# Module_MCU_M5Stack.net
KiCad netlist of a schematic drawn in EAGLE
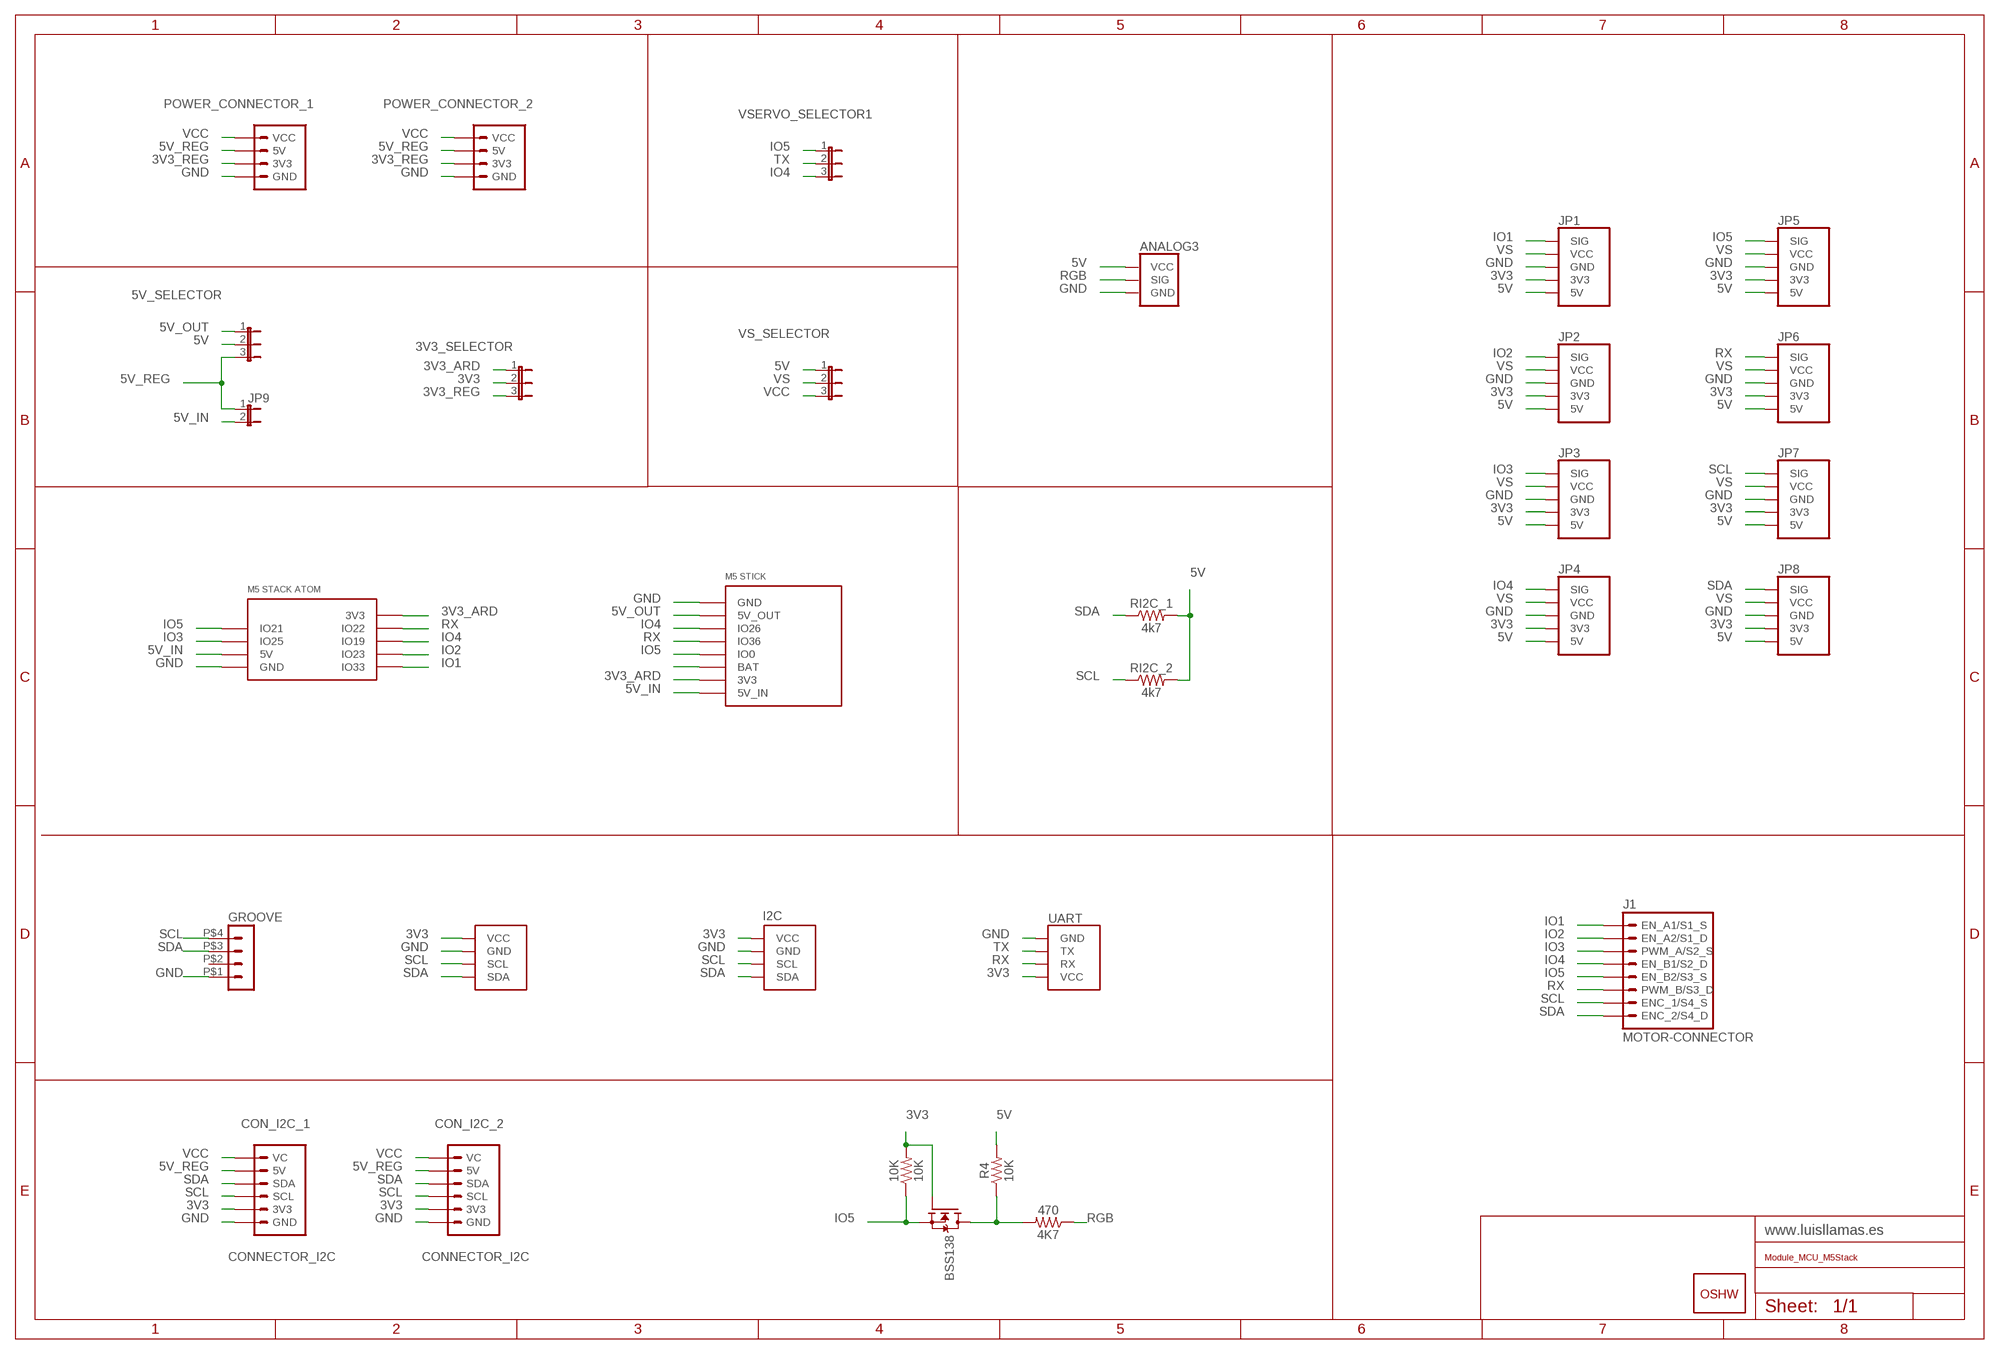
[diagram p0: schematic, sheet 1]

(export (version "E")
  (design (tool "Eeschema 10.0.6"))
  (components
    (comp (ref "3V3_SELECTOR")
      (value "JUMPER_3")
      (footprint "eagle-import:JUMPER_3")
      (libsource (lib "eagle-import") (part "JUMPER_3"))
    )
    (comp (ref "4K7")
      (value "470")
      (footprint "eagle-import:0805")
      (libsource (lib "eagle-import") (part "RESISTOR0805"))
    )
    (comp (ref "5V_SELECTOR")
      (value "JUMPER_3")
      (footprint "eagle-import:JUMPER_3")
      (libsource (lib "eagle-import") (part "JUMPER_3"))
    )
    (comp (ref "10K")
      (value "10K")
      (footprint "eagle-import:0805")
      (libsource (lib "eagle-import") (part "RESISTOR0805"))
    )
    (comp (ref "ANALOG3")
      (value "LDR/OCT")
      (footprint "eagle-import:LDR")
      (libsource (lib "eagle-import") (part "LDR/OCT"))
    )
    (comp (ref "BSS138")
      (value "MOSFET-N-SOT23")
      (footprint "eagle-import:SOT23")
      (libsource (lib "eagle-import") (part "MOSFET-N-SOT23"))
    )
    (comp (ref "CON_I2C_1")
      (value "CONNECTOR_I2C")
      (footprint "eagle-import:CONNECTOR_I2C")
      (libsource (lib "eagle-import") (part "CONNECTOR_I2C"))
    )
    (comp (ref "CON_I2C_2")
      (value "CONNECTOR_I2C")
      (footprint "eagle-import:CONNECTOR_I2C")
      (libsource (lib "eagle-import") (part "CONNECTOR_I2C"))
    )
    (comp (ref "GOLD_ORB_SM1")
      (value "OSHWLOGO_GOLD_ORB_MED")
      (footprint "eagle-import:OSHW1")
      (libsource (lib "eagle-import") (part "OSHWLOGO_GOLD_ORB_MED"))
    )
    (comp (ref "GROOVE")
      (value "GROOVE")
      (footprint "eagle-import:GROOVE")
      (libsource (lib "eagle-import") (part "GROOVE"))
    )
    (comp (ref "I2C_1")
      (value "I2C")
      (footprint "eagle-import:I2C_VCC_GND_SCL_SDA")
      (libsource (lib "eagle-import") (part "GENERIC_I2CVCC_GND_SCL_SDA"))
    )
    (comp (ref "I2C_2")
      (value "GENERIC_I2CVCC_GND_SCL_SDA")
      (footprint "eagle-import:I2C_VCC_GND_SCL_SDA")
      (libsource (lib "eagle-import") (part "GENERIC_I2CVCC_GND_SCL_SDA"))
    )
    (comp (ref "J1")
      (value "MOTOR-CONNECTOR")
      (footprint "eagle-import:MOTOR-CONNECTOR")
      (libsource (lib "eagle-import") (part "MOTOR-CONNECTOR"))
    )
    (comp (ref "JP1")
      (value "SERVO_5")
      (footprint "eagle-import:SERVO_5")
      (libsource (lib "eagle-import") (part "SERVO_5"))
    )
    (comp (ref "JP2")
      (value "SERVO_5")
      (footprint "eagle-import:SERVO_5")
      (libsource (lib "eagle-import") (part "SERVO_5"))
    )
    (comp (ref "JP3")
      (value "SERVO_5")
      (footprint "eagle-import:SERVO_5")
      (libsource (lib "eagle-import") (part "SERVO_5"))
    )
    (comp (ref "JP4")
      (value "SERVO_5")
      (footprint "eagle-import:SERVO_5")
      (libsource (lib "eagle-import") (part "SERVO_5"))
    )
    (comp (ref "JP5")
      (value "SERVO_5")
      (footprint "eagle-import:SERVO_5")
      (libsource (lib "eagle-import") (part "SERVO_5"))
    )
    (comp (ref "JP6")
      (value "SERVO_5")
      (footprint "eagle-import:SERVO_5")
      (libsource (lib "eagle-import") (part "SERVO_5"))
    )
    (comp (ref "JP7")
      (value "SERVO_5")
      (footprint "eagle-import:SERVO_5")
      (libsource (lib "eagle-import") (part "SERVO_5"))
    )
    (comp (ref "JP8")
      (value "SERVO_5")
      (footprint "eagle-import:SERVO_5")
      (libsource (lib "eagle-import") (part "SERVO_5"))
    )
    (comp (ref "JP9")
      (value "JUMPER_2PTH")
      (footprint "eagle-import:JUMPER_2")
      (libsource (lib "eagle-import") (part "JUMPER_2PTH"))
    )
    (comp (ref "POWER_CONNECTOR_1")
      (value "POWER-CONNECTOR")
      (footprint "eagle-import:POWER-CONNECTOR")
      (libsource (lib "eagle-import") (part "POWER-CONNECTOR"))
    )
    (comp (ref "POWER_CONNECTOR_2")
      (value "POWER-CONNECTOR")
      (footprint "eagle-import:POWER-CONNECTOR")
      (libsource (lib "eagle-import") (part "POWER-CONNECTOR"))
    )
    (comp (ref "R4")
      (value "10K")
      (footprint "eagle-import:0805")
      (libsource (lib "eagle-import") (part "RESISTOR0805"))
    )
    (comp (ref "RI2C_1")
      (value "4k7")
      (footprint "eagle-import:1206")
      (libsource (lib "eagle-import") (part "RESISTOR1206"))
    )
    (comp (ref "RI2C_2")
      (value "4k7")
      (footprint "eagle-import:1206")
      (libsource (lib "eagle-import") (part "RESISTOR1206"))
    )
    (comp (ref "U$1")
      (value "M5-STACK-ATOM")
      (footprint "eagle-import:M5-STACK-ATOM")
      (libsource (lib "eagle-import") (part "M5-STACK-ATOM"))
    )
    (comp (ref "U$2")
      (value "M5-STICK")
      (footprint "eagle-import:M5-STICK")
      (libsource (lib "eagle-import") (part "M5-STICK"))
    )
    (comp (ref "UART")
      (value "UART")
      (footprint "eagle-import:GENERIC_UART")
      (libsource (lib "eagle-import") (part "GENERIC_UARTGND_TX_RX_VCC"))
    )
    (comp (ref "VSERVO_SELECTOR1")
      (value "JUMPER_3")
      (footprint "eagle-import:JUMPER_3")
      (libsource (lib "eagle-import") (part "JUMPER_3"))
    )
    (comp (ref "VS_SELECTOR")
      (value "JUMPER_3")
      (footprint "eagle-import:JUMPER_3")
      (libsource (lib "eagle-import") (part "JUMPER_3"))
    )
  )
  (nets
    (net (code "1") (name "/3V3") (class "Default")
      (node (ref "10K") (pin "2") (pinfunction "2_2") (pintype "passive"))
      (node (ref "3V3_SELECTOR") (pin "2") (pinfunction "2_2") (pintype "passive"))
      (node (ref "BSS138") (pin "1") (pinfunction "G_1") (pintype "passive"))
      (node (ref "CON_I2C_1") (pin "3V3") (pinfunction "3V3_3V3") (pintype "passive"))
      (node (ref "CON_I2C_2") (pin "3V3") (pinfunction "3V3_3V3") (pintype "passive"))
      (node (ref "I2C_1") (pin "VCC") (pinfunction "VCC_VCC") (pintype "power_in"))
      (node (ref "I2C_2") (pin "VCC") (pinfunction "VCC_VCC") (pintype "power_in"))
      (node (ref "JP1") (pin "3V3") (pinfunction "3V3_3V3") (pintype "power_in"))
      (node (ref "JP2") (pin "3V3") (pinfunction "3V3_3V3") (pintype "power_in"))
      (node (ref "JP3") (pin "3V3") (pinfunction "3V3_3V3") (pintype "power_in"))
      (node (ref "JP4") (pin "3V3") (pinfunction "3V3_3V3") (pintype "power_in"))
      (node (ref "JP5") (pin "3V3") (pinfunction "3V3_3V3") (pintype "power_in"))
      (node (ref "JP6") (pin "3V3") (pinfunction "3V3_3V3") (pintype "power_in"))
      (node (ref "JP7") (pin "3V3") (pinfunction "3V3_3V3") (pintype "power_in"))
      (node (ref "JP8") (pin "3V3") (pinfunction "3V3_3V3") (pintype "power_in"))
      (node (ref "UART") (pin "VCC") (pinfunction "VCC_VCC") (pintype "bidirectional"))
    )
    (net (code "2") (name "/3V3_ARD") (class "Default")
      (node (ref "3V3_SELECTOR") (pin "1") (pinfunction "1_1") (pintype "passive"))
      (node (ref "U$1") (pin "3V3") (pinfunction "3V3_3V3") (pintype "bidirectional"))
      (node (ref "U$2") (pin "3V3") (pinfunction "3V3_3V3") (pintype "bidirectional"))
    )
    (net (code "3") (name "/3V3_REG") (class "Default")
      (node (ref "3V3_SELECTOR") (pin "3") (pinfunction "3_3") (pintype "passive"))
      (node (ref "POWER_CONNECTOR_1") (pin "3V3") (pinfunction "3V3_3V3") (pintype "passive"))
      (node (ref "POWER_CONNECTOR_2") (pin "3V3") (pinfunction "3V3_3V3") (pintype "passive"))
    )
    (net (code "4") (name "/5V") (class "Default")
      (node (ref "5V_SELECTOR") (pin "2") (pinfunction "2_2") (pintype "passive"))
      (node (ref "ANALOG3") (pin "VCC") (pinfunction "VCC_VCC") (pintype "power_in"))
      (node (ref "JP1") (pin "5V") (pinfunction "5V_5V") (pintype "power_in"))
      (node (ref "JP2") (pin "5V") (pinfunction "5V_5V") (pintype "power_in"))
      (node (ref "JP3") (pin "5V") (pinfunction "5V_5V") (pintype "power_in"))
      (node (ref "JP4") (pin "5V") (pinfunction "5V_5V") (pintype "power_in"))
      (node (ref "JP5") (pin "5V") (pinfunction "5V_5V") (pintype "power_in"))
      (node (ref "JP6") (pin "5V") (pinfunction "5V_5V") (pintype "power_in"))
      (node (ref "JP7") (pin "5V") (pinfunction "5V_5V") (pintype "power_in"))
      (node (ref "JP8") (pin "5V") (pinfunction "5V_5V") (pintype "power_in"))
      (node (ref "R4") (pin "2") (pinfunction "2_2") (pintype "passive"))
      (node (ref "RI2C_1") (pin "2") (pinfunction "2_2") (pintype "passive"))
      (node (ref "RI2C_2") (pin "2") (pinfunction "2_2") (pintype "passive"))
      (node (ref "VS_SELECTOR") (pin "1") (pinfunction "1_1") (pintype "passive"))
    )
    (net (code "5") (name "/5V_IN") (class "Default")
      (node (ref "JP9") (pin "2") (pinfunction "2_2") (pintype "passive"))
      (node (ref "U$1") (pin "5V") (pinfunction "5V_5V") (pintype "bidirectional"))
      (node (ref "U$2") (pin "5V_IN") (pinfunction "5V_IN_5V_IN") (pintype "bidirectional"))
    )
    (net (code "6") (name "/5V_OUT") (class "Default")
      (node (ref "5V_SELECTOR") (pin "1") (pinfunction "1_1") (pintype "passive"))
      (node (ref "U$2") (pin "5V_OUT") (pinfunction "5V_OUT_5V_OUT") (pintype "bidirectional"))
    )
    (net (code "7") (name "/5V_REG") (class "Default")
      (node (ref "5V_SELECTOR") (pin "3") (pinfunction "3_3") (pintype "passive"))
      (node (ref "CON_I2C_1") (pin "5V") (pinfunction "5V_5V") (pintype "passive"))
      (node (ref "CON_I2C_2") (pin "5V") (pinfunction "5V_5V") (pintype "passive"))
      (node (ref "JP9") (pin "1") (pinfunction "1_1") (pintype "passive"))
      (node (ref "POWER_CONNECTOR_1") (pin "5V") (pinfunction "5V_5V") (pintype "passive"))
      (node (ref "POWER_CONNECTOR_2") (pin "5V") (pinfunction "5V_5V") (pintype "passive"))
    )
    (net (code "8") (name "/GND") (class "Default")
      (node (ref "ANALOG3") (pin "GND") (pinfunction "GND_GND") (pintype "power_in"))
      (node (ref "CON_I2C_1") (pin "GND") (pinfunction "GND_GND") (pintype "passive"))
      (node (ref "CON_I2C_2") (pin "GND") (pinfunction "GND_GND") (pintype "passive"))
      (node (ref "GROOVE") (pin "P$1") (pinfunction "1_P$1") (pintype "passive"))
      (node (ref "I2C_1") (pin "GND") (pinfunction "GND_GND") (pintype "power_in"))
      (node (ref "I2C_2") (pin "GND") (pinfunction "GND_GND") (pintype "power_in"))
      (node (ref "JP1") (pin "GND") (pinfunction "GND_GND") (pintype "power_in"))
      (node (ref "JP2") (pin "GND") (pinfunction "GND_GND") (pintype "power_in"))
      (node (ref "JP3") (pin "GND") (pinfunction "GND_GND") (pintype "power_in"))
      (node (ref "JP4") (pin "GND") (pinfunction "GND_GND") (pintype "power_in"))
      (node (ref "JP5") (pin "GND") (pinfunction "GND_GND") (pintype "power_in"))
      (node (ref "JP6") (pin "GND") (pinfunction "GND_GND") (pintype "power_in"))
      (node (ref "JP7") (pin "GND") (pinfunction "GND_GND") (pintype "power_in"))
      (node (ref "JP8") (pin "GND") (pinfunction "GND_GND") (pintype "power_in"))
      (node (ref "POWER_CONNECTOR_1") (pin "GND") (pinfunction "GND_GND") (pintype "passive"))
      (node (ref "POWER_CONNECTOR_2") (pin "GND") (pinfunction "GND_GND") (pintype "passive"))
      (node (ref "U$1") (pin "GND") (pinfunction "GND_GND") (pintype "bidirectional"))
      (node (ref "U$2") (pin "GND") (pinfunction "GND_GND") (pintype "bidirectional"))
      (node (ref "UART") (pin "GND") (pinfunction "GND_GND") (pintype "power_in"))
    )
    (net (code "9") (name "/IO1") (class "Default")
      (node (ref "J1") (pin "EN_A1/S1_S") (pinfunction "EN_A1/S1_S_EN_A1/S1_S") (pintype "passive"))
      (node (ref "JP1") (pin "SIG") (pinfunction "SIG_SIG") (pintype "bidirectional"))
      (node (ref "U$1") (pin "IO33") (pinfunction "IO33_IO33") (pintype "bidirectional"))
    )
    (net (code "10") (name "/IO2") (class "Default")
      (node (ref "J1") (pin "EN_A2/S1_D") (pinfunction "EN_A2/S1_D_EN_A2/S1_D") (pintype "passive"))
      (node (ref "JP2") (pin "SIG") (pinfunction "SIG_SIG") (pintype "bidirectional"))
      (node (ref "U$1") (pin "IO23") (pinfunction "IO23_IO23") (pintype "bidirectional"))
    )
    (net (code "11") (name "/IO3") (class "Default")
      (node (ref "J1") (pin "PWM_A/S2_S") (pinfunction "PWM_A/S2_S_PWM_A/S2_S") (pintype "passive"))
      (node (ref "JP3") (pin "SIG") (pinfunction "SIG_SIG") (pintype "bidirectional"))
      (node (ref "U$1") (pin "IO25") (pinfunction "IO25_IO25") (pintype "bidirectional"))
    )
    (net (code "12") (name "/IO4") (class "Default")
      (node (ref "J1") (pin "EN_B1/S2_D") (pinfunction "EN_B1/S2_D_EN_B1/S2_D") (pintype "passive"))
      (node (ref "JP4") (pin "SIG") (pinfunction "SIG_SIG") (pintype "bidirectional"))
      (node (ref "U$1") (pin "IO19") (pinfunction "IO19_IO19") (pintype "bidirectional"))
      (node (ref "U$2") (pin "IO26") (pinfunction "IO26_IO26") (pintype "bidirectional"))
      (node (ref "VSERVO_SELECTOR1") (pin "3") (pinfunction "3_3") (pintype "passive"))
    )
    (net (code "13") (name "/IO5") (class "Default")
      (node (ref "10K") (pin "1") (pinfunction "1_1") (pintype "passive"))
      (node (ref "BSS138") (pin "2") (pinfunction "S_2") (pintype "passive"))
      (node (ref "J1") (pin "EN_B2/S3_S") (pinfunction "EN_B2/S3_S_EN_B2/S3_S") (pintype "passive"))
      (node (ref "JP5") (pin "SIG") (pinfunction "SIG_SIG") (pintype "bidirectional"))
      (node (ref "U$1") (pin "IO21") (pinfunction "IO21_IO21") (pintype "bidirectional"))
      (node (ref "U$2") (pin "IO0") (pinfunction "IO0_IO0") (pintype "bidirectional"))
      (node (ref "VSERVO_SELECTOR1") (pin "1") (pinfunction "1_1") (pintype "passive"))
    )
    (net (code "14") (name "/RGB") (class "Default")
      (node (ref "4K7") (pin "1") (pinfunction "1_1") (pintype "passive"))
      (node (ref "ANALOG3") (pin "SIG") (pinfunction "SIG_SIG") (pintype "bidirectional"))
    )
    (net (code "15") (name "/RX") (class "Default")
      (node (ref "J1") (pin "PWM_B/S3_D") (pinfunction "PWM_B/S3_D_PWM_B/S3_D") (pintype "passive"))
      (node (ref "JP6") (pin "SIG") (pinfunction "SIG_SIG") (pintype "bidirectional"))
      (node (ref "U$1") (pin "IO22") (pinfunction "IO22_IO22") (pintype "bidirectional"))
      (node (ref "U$2") (pin "IO36") (pinfunction "IO36_IO36") (pintype "bidirectional"))
      (node (ref "UART") (pin "RX") (pinfunction "RX_RX") (pintype "bidirectional"))
    )
    (net (code "16") (name "/SCL") (class "Default")
      (node (ref "CON_I2C_1") (pin "SCL") (pinfunction "SCL_SCL") (pintype "passive"))
      (node (ref "CON_I2C_2") (pin "SCL") (pinfunction "SCL_SCL") (pintype "passive"))
      (node (ref "GROOVE") (pin "P$4") (pinfunction "4_P$4") (pintype "passive"))
      (node (ref "I2C_1") (pin "SCL") (pinfunction "SCL_SCL") (pintype "bidirectional"))
      (node (ref "I2C_2") (pin "SCL") (pinfunction "SCL_SCL") (pintype "bidirectional"))
      (node (ref "J1") (pin "ENC_1/S4_S") (pinfunction "ENC_1/S4_S_ENC_1/S4_S") (pintype "passive"))
      (node (ref "JP7") (pin "SIG") (pinfunction "SIG_SIG") (pintype "bidirectional"))
      (node (ref "RI2C_2") (pin "1") (pinfunction "1_1") (pintype "passive"))
    )
    (net (code "17") (name "/SDA") (class "Default")
      (node (ref "CON_I2C_1") (pin "SDA") (pinfunction "SDA_SDA") (pintype "passive"))
      (node (ref "CON_I2C_2") (pin "SDA") (pinfunction "SDA_SDA") (pintype "passive"))
      (node (ref "GROOVE") (pin "P$3") (pinfunction "3_P$3") (pintype "passive"))
      (node (ref "I2C_1") (pin "SDA") (pinfunction "SDA_SDA") (pintype "bidirectional"))
      (node (ref "I2C_2") (pin "SDA") (pinfunction "SDA_SDA") (pintype "bidirectional"))
      (node (ref "J1") (pin "ENC_2/S4_D") (pinfunction "ENC_2/S4_D_ENC_2/S4_D") (pintype "passive"))
      (node (ref "JP8") (pin "SIG") (pinfunction "SIG_SIG") (pintype "bidirectional"))
      (node (ref "RI2C_1") (pin "1") (pinfunction "1_1") (pintype "passive"))
    )
    (net (code "18") (name "/TX") (class "Default")
      (node (ref "UART") (pin "TX") (pinfunction "TX_TX") (pintype "power_in"))
      (node (ref "VSERVO_SELECTOR1") (pin "2") (pinfunction "2_2") (pintype "passive"))
    )
    (net (code "19") (name "/VCC") (class "Default")
      (node (ref "CON_I2C_1") (pin "VC") (pinfunction "VC_VC") (pintype "passive"))
      (node (ref "CON_I2C_2") (pin "VC") (pinfunction "VC_VC") (pintype "passive"))
      (node (ref "POWER_CONNECTOR_1") (pin "VCC") (pinfunction "VCC_VCC") (pintype "passive"))
      (node (ref "POWER_CONNECTOR_2") (pin "VCC") (pinfunction "VCC_VCC") (pintype "passive"))
      (node (ref "VS_SELECTOR") (pin "3") (pinfunction "3_3") (pintype "passive"))
    )
    (net (code "20") (name "/VS") (class "Default")
      (node (ref "JP1") (pin "VCC") (pinfunction "VCC_VCC") (pintype "power_in"))
      (node (ref "JP2") (pin "VCC") (pinfunction "VCC_VCC") (pintype "power_in"))
      (node (ref "JP3") (pin "VCC") (pinfunction "VCC_VCC") (pintype "power_in"))
      (node (ref "JP4") (pin "VCC") (pinfunction "VCC_VCC") (pintype "power_in"))
      (node (ref "JP5") (pin "VCC") (pinfunction "VCC_VCC") (pintype "power_in"))
      (node (ref "JP6") (pin "VCC") (pinfunction "VCC_VCC") (pintype "power_in"))
      (node (ref "JP7") (pin "VCC") (pinfunction "VCC_VCC") (pintype "power_in"))
      (node (ref "JP8") (pin "VCC") (pinfunction "VCC_VCC") (pintype "power_in"))
      (node (ref "VS_SELECTOR") (pin "2") (pinfunction "2_2") (pintype "passive"))
    )
    (net (code "21") (name "Net-(BSS138-D)") (class "Default")
      (node (ref "4K7") (pin "2") (pinfunction "2_2") (pintype "passive"))
      (node (ref "BSS138") (pin "3") (pinfunction "D_3") (pintype "passive"))
      (node (ref "R4") (pin "1") (pinfunction "1_1") (pintype "passive"))
    )
    (net (code "22") (name "unconnected-(GROOVE-2-PadP$2)") (class "Default")
      (node (ref "GROOVE") (pin "P$2") (pinfunction "2_P$2") (pintype "passive"))
    )
    (net (code "23") (name "unconnected-(U$2-PadBAT)") (class "Default")
      (node (ref "U$2") (pin "BAT") (pinfunction "BAT_BAT") (pintype "bidirectional"))
    )
  )
)
